# LM2596.net
KiCad netlist of a schematic drawn in Altium Designer
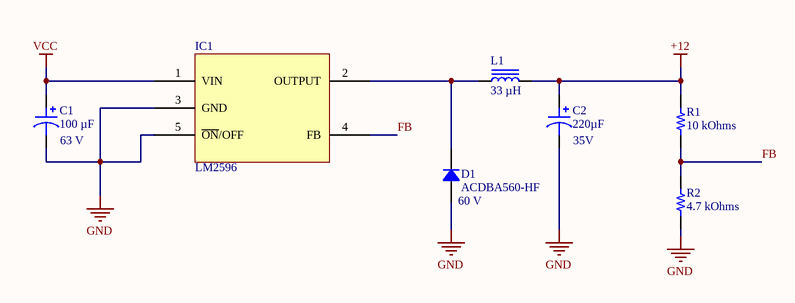
[diagram p0: LM2596.SchDoc]

(export (version "E")
  (design (tool "Eeschema 10.0.6"))
  (components
    (comp (ref "C1")
      (value "100 µF")
      (footprint "CAP ALSMD POLY 8.3MM H10.5MM")
      (description "CAP ALUM HYB 100UF 20% 63V SMD")
      (fields
        (field (name "PART NUMBER") "HHXJ630ARA101MJA0G")
        (field (name "MANUFACTURER") "Chemi-Con")
        (field (name "VOLTAGE - RATED") "63 V")
      )
      (libsource (lib "Celestial Altium Library - altium_library") (part "Polarised Capacitor"))
    )
    (comp (ref "C2")
      (value "220µF")
      (footprint "CAP ALSMD 8.3MM H10.5MM")
      (description "CAP ALUM 220UF 20% 35V SMD")
      (fields
        (field (name "PART NUMBER") "UUR1V221MNL6GS")
        (field (name "MANUFACTURER") "Nichicon")
        (field (name "VOLTAGE - RATED") "35V")
      )
      (libsource (lib "Celestial Altium Library - altium_library") (part "Polarised Capacitor"))
    )
    (comp (ref "D1")
      (value "ACDBA560-HF")
      (footprint "DO214AC SMA")
      (description "DIODE SCHOTTKY 60V 5A DO214AC")
      (fields
        (field (name "MANUFACTURER") "Comchip Technology")
        (field (name "VOLTAGE - DC REVERSE (VR) (MAX)") "60 V")
      )
      (libsource (lib "Celestial Altium Library - altium_library") (part "Diode"))
    )
    (comp (ref "IC1") (value "LM2596") (footprint "D2PAK") (libsource (lib "Buck_Converter") (part "LM2598")))
    (comp (ref "L1")
      (value "33 µH")
      (footprint "BOURNS SRR1280")
      (description "FIXED IND 33UH 3.5A 57 MOHM SMD")
      (fields (field (name "PART NUMBER") "SRR1280-330M") (field (name "MANUFACTURER") "Bourns Inc."))
      (libsource (lib "Celestial Altium Library - altium_library") (part "Inductor"))
    )
    (comp (ref "R1")
      (value "10 kOhms")
      (footprint "RES 0805_2012")
      (description "RES 10K OHM 1% 1/4W 0805")
      (fields
        (field (name "PART NUMBER") "RNCP0805FTD10K0")
        (field (name "MANUFACTURER") "Stackpole Electronics Inc")
      )
      (libsource (lib "Celestial Altium Library - altium_library") (part "Resistor"))
    )
    (comp (ref "R2")
      (value "4.7 kOhms")
      (footprint "RES 0805_2012")
      (description "RES SMD 4.7K OHM 1% 1/2W 0805")
      (fields (field (name "PART NUMBER") "CRCW08054K70FKEAHP") (field (name "MANUFACTURER") "Vishay Dale"))
      (libsource (lib "Celestial Altium Library - altium_library") (part "Resistor"))
    )
  )
  (nets
    (net (code "1") (name "+12") (class "Default")
      (node (ref "C2") (pin "1") (pinfunction "1_1") (pintype "passive"))
      (node (ref "L1") (pin "2") (pinfunction "2_2") (pintype "passive"))
      (node (ref "R1") (pin "2") (pinfunction "2_2") (pintype "passive"))
    )
    (net (code "2") (name "/FB") (class "Default")
      (node (ref "IC1") (pin "4") (pinfunction "FB_4") (pintype "passive"))
      (node (ref "R1") (pin "1") (pinfunction "1_1") (pintype "passive"))
      (node (ref "R2") (pin "2") (pinfunction "2_2") (pintype "passive"))
    )
    (net (code "3") (name "GND") (class "Default")
      (node (ref "C1") (pin "2") (pinfunction "2_2") (pintype "passive"))
      (node (ref "C2") (pin "2") (pinfunction "2_2") (pintype "passive"))
      (node (ref "D1") (pin "1") (pinfunction "1_1") (pintype "passive"))
      (node (ref "IC1") (pin "3") (pinfunction "GND_3") (pintype "passive"))
      (node (ref "IC1") (pin "5") (pinfunction "~{ON}/OFF_5") (pintype "passive"))
      (node (ref "R2") (pin "1") (pinfunction "1_1") (pintype "passive"))
    )
    (net (code "4") (name "Net-(IC1-OUTPUT)") (class "Default")
      (node (ref "D1") (pin "2") (pinfunction "2_2") (pintype "passive"))
      (node (ref "IC1") (pin "2") (pinfunction "OUTPUT_2") (pintype "passive"))
      (node (ref "L1") (pin "1") (pinfunction "1_1") (pintype "passive"))
    )
    (net (code "5") (name "VCC") (class "Default")
      (node (ref "C1") (pin "1") (pinfunction "1_1") (pintype "passive"))
      (node (ref "IC1") (pin "1") (pinfunction "VIN_1") (pintype "passive"))
    )
  )
)
